# FPGA_PWR.net
KiCad netlist of a schematic drawn in Altium Designer
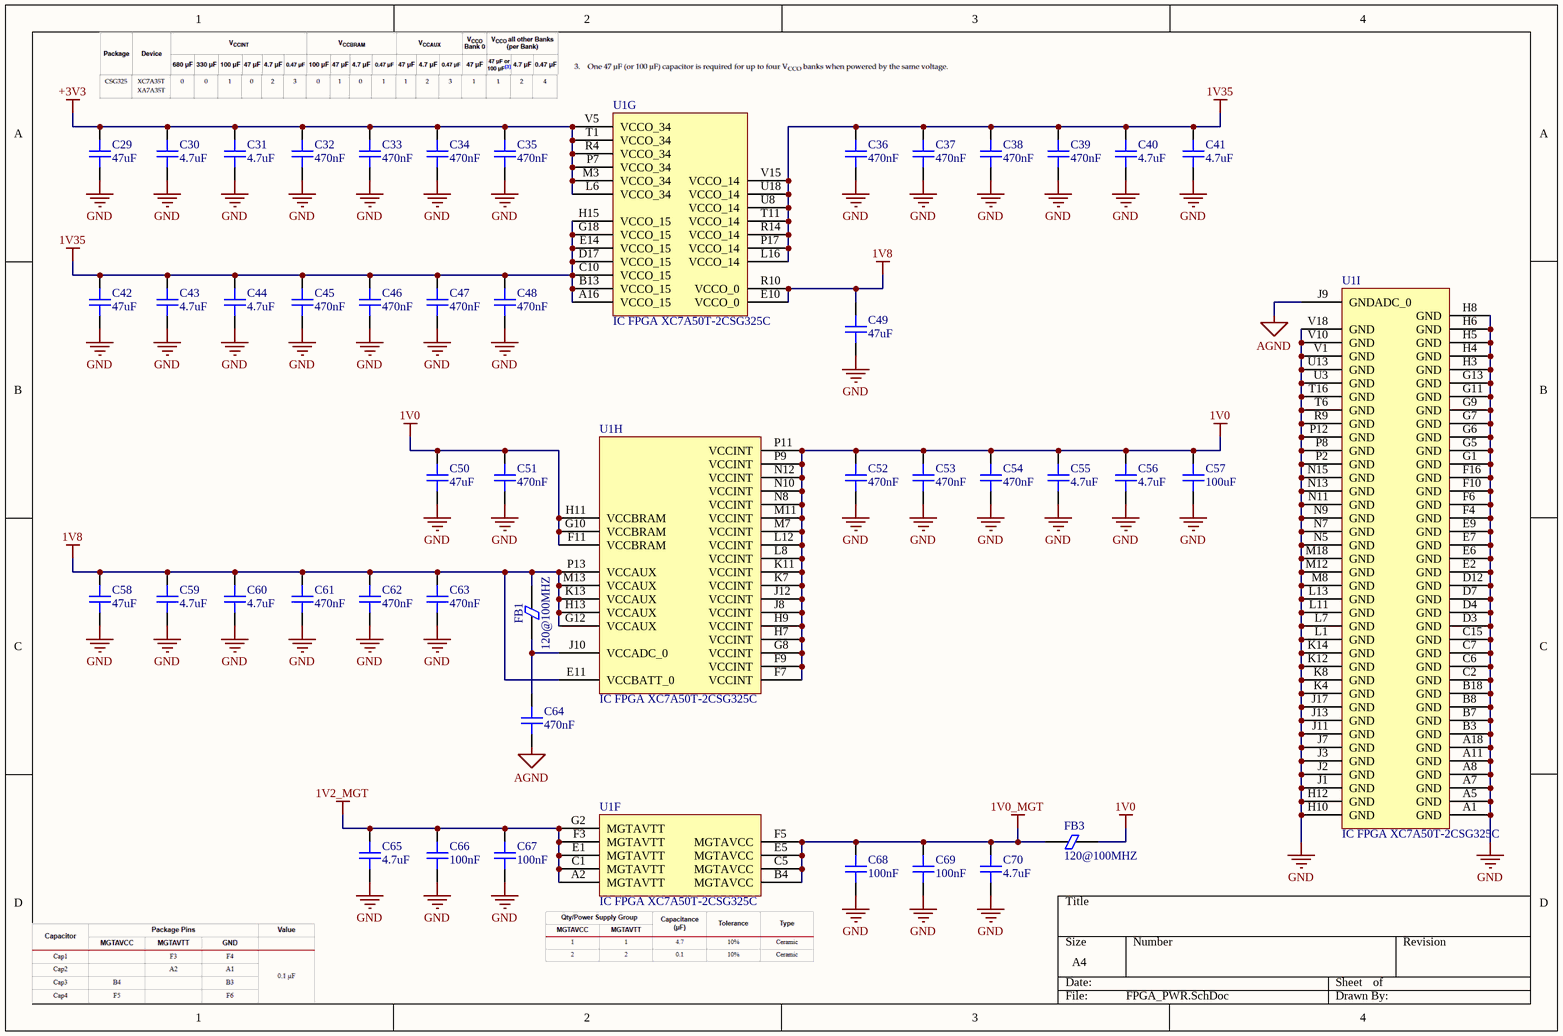
[diagram p0: FPGA_PWR.SchDoc]

(export (version "E")
  (design (tool "Eeschema 10.0.6"))
  (components
    (comp (ref "C29")
      (value "47uF")
      (footprint "GEN_C_0805")
      (libsource (lib "DSO") (part "CAP 47uF 6.3V X5R 0805"))
    )
    (comp (ref "C30")
      (value "4.7uF")
      (footprint "GEN_C_0402")
      (libsource (lib "DSO") (part "CAP 4.7uF 6.3V X5R 0402"))
    )
    (comp (ref "C31")
      (value "4.7uF")
      (footprint "GEN_C_0402")
      (libsource (lib "DSO") (part "CAP 4.7uF 6.3V X5R 0402"))
    )
    (comp (ref "C32")
      (value "470nF")
      (footprint "GEN_C_0201")
      (libsource (lib "DSO") (part "CAP 470nF 6.3V X5R 0201"))
    )
    (comp (ref "C33")
      (value "470nF")
      (footprint "GEN_C_0201")
      (libsource (lib "DSO") (part "CAP 470nF 6.3V X5R 0201"))
    )
    (comp (ref "C34")
      (value "470nF")
      (footprint "GEN_C_0201")
      (libsource (lib "DSO") (part "CAP 470nF 6.3V X5R 0201"))
    )
    (comp (ref "C35")
      (value "470nF")
      (footprint "GEN_C_0201")
      (libsource (lib "DSO") (part "CAP 470nF 6.3V X5R 0201"))
    )
    (comp (ref "C36")
      (value "470nF")
      (footprint "GEN_C_0201")
      (libsource (lib "DSO") (part "CAP 470nF 6.3V X5R 0201"))
    )
    (comp (ref "C37")
      (value "470nF")
      (footprint "GEN_C_0201")
      (libsource (lib "DSO") (part "CAP 470nF 6.3V X5R 0201"))
    )
    (comp (ref "C38")
      (value "470nF")
      (footprint "GEN_C_0201")
      (libsource (lib "DSO") (part "CAP 470nF 6.3V X5R 0201"))
    )
    (comp (ref "C39")
      (value "470nF")
      (footprint "GEN_C_0201")
      (libsource (lib "DSO") (part "CAP 470nF 6.3V X5R 0201"))
    )
    (comp (ref "C40")
      (value "4.7uF")
      (footprint "GEN_C_0402")
      (libsource (lib "DSO") (part "CAP 4.7uF 6.3V X5R 0402"))
    )
    (comp (ref "C41")
      (value "4.7uF")
      (footprint "GEN_C_0402")
      (libsource (lib "DSO") (part "CAP 4.7uF 6.3V X5R 0402"))
    )
    (comp (ref "C42")
      (value "47uF")
      (footprint "GEN_C_0805")
      (libsource (lib "DSO") (part "CAP 47uF 6.3V X5R 0805"))
    )
    (comp (ref "C43")
      (value "4.7uF")
      (footprint "GEN_C_0402")
      (libsource (lib "DSO") (part "CAP 4.7uF 6.3V X5R 0402"))
    )
    (comp (ref "C44")
      (value "4.7uF")
      (footprint "GEN_C_0402")
      (libsource (lib "DSO") (part "CAP 4.7uF 6.3V X5R 0402"))
    )
    (comp (ref "C45")
      (value "470nF")
      (footprint "GEN_C_0201")
      (libsource (lib "DSO") (part "CAP 470nF 6.3V X5R 0201"))
    )
    (comp (ref "C46")
      (value "470nF")
      (footprint "GEN_C_0201")
      (libsource (lib "DSO") (part "CAP 470nF 6.3V X5R 0201"))
    )
    (comp (ref "C47")
      (value "470nF")
      (footprint "GEN_C_0201")
      (libsource (lib "DSO") (part "CAP 470nF 6.3V X5R 0201"))
    )
    (comp (ref "C48")
      (value "470nF")
      (footprint "GEN_C_0201")
      (libsource (lib "DSO") (part "CAP 470nF 6.3V X5R 0201"))
    )
    (comp (ref "C49")
      (value "47uF")
      (footprint "GEN_C_0805")
      (libsource (lib "DSO") (part "CAP 47uF 6.3V X5R 0805"))
    )
    (comp (ref "C50")
      (value "47uF")
      (footprint "GEN_C_0805")
      (libsource (lib "DSO") (part "CAP 47uF 6.3V X5R 0805"))
    )
    (comp (ref "C51")
      (value "470nF")
      (footprint "GEN_C_0201")
      (libsource (lib "DSO") (part "CAP 470nF 6.3V X5R 0201"))
    )
    (comp (ref "C52")
      (value "470nF")
      (footprint "GEN_C_0201")
      (libsource (lib "DSO") (part "CAP 470nF 6.3V X5R 0201"))
    )
    (comp (ref "C53")
      (value "470nF")
      (footprint "GEN_C_0201")
      (libsource (lib "DSO") (part "CAP 470nF 6.3V X5R 0201"))
    )
    (comp (ref "C54")
      (value "470nF")
      (footprint "GEN_C_0201")
      (libsource (lib "DSO") (part "CAP 470nF 6.3V X5R 0201"))
    )
    (comp (ref "C55")
      (value "4.7uF")
      (footprint "GEN_C_0402")
      (libsource (lib "DSO") (part "CAP 4.7uF 6.3V X5R 0402"))
    )
    (comp (ref "C56")
      (value "4.7uF")
      (footprint "GEN_C_0402")
      (libsource (lib "DSO") (part "CAP 4.7uF 6.3V X5R 0402"))
    )
    (comp (ref "C57")
      (value "100uF")
      (footprint "GEN_C_1210")
      (libsource (lib "DSO") (part "CAP 100uF 6.3V X5R 1210"))
    )
    (comp (ref "C58")
      (value "47uF")
      (footprint "GEN_C_0805")
      (libsource (lib "DSO") (part "CAP 47uF 6.3V X5R 0805"))
    )
    (comp (ref "C59")
      (value "4.7uF")
      (footprint "GEN_C_0402")
      (libsource (lib "DSO") (part "CAP 4.7uF 6.3V X5R 0402"))
    )
    (comp (ref "C60")
      (value "4.7uF")
      (footprint "GEN_C_0402")
      (libsource (lib "DSO") (part "CAP 4.7uF 6.3V X5R 0402"))
    )
    (comp (ref "C61")
      (value "470nF")
      (footprint "GEN_C_0201")
      (libsource (lib "DSO") (part "CAP 470nF 6.3V X5R 0201"))
    )
    (comp (ref "C62")
      (value "470nF")
      (footprint "GEN_C_0201")
      (libsource (lib "DSO") (part "CAP 470nF 6.3V X5R 0201"))
    )
    (comp (ref "C63")
      (value "470nF")
      (footprint "GEN_C_0201")
      (libsource (lib "DSO") (part "CAP 470nF 6.3V X5R 0201"))
    )
    (comp (ref "C64")
      (value "470nF")
      (footprint "GEN_C_0201")
      (libsource (lib "DSO") (part "CAP 470nF 6.3V X5R 0201"))
    )
    (comp (ref "C65")
      (value "4.7uF")
      (footprint "GEN_C_0402")
      (libsource (lib "DSO") (part "CAP 4.7uF 6.3V X5R 0402"))
    )
    (comp (ref "C66")
      (value "100nF")
      (footprint "GEN_C_0201")
      (libsource (lib "DSO") (part "CAP 100nF 6.3V X5R 0201"))
    )
    (comp (ref "C67")
      (value "100nF")
      (footprint "GEN_C_0201")
      (libsource (lib "DSO") (part "CAP 100nF 6.3V X5R 0201"))
    )
    (comp (ref "C68")
      (value "100nF")
      (footprint "GEN_C_0201")
      (libsource (lib "DSO") (part "CAP 100nF 6.3V X5R 0201"))
    )
    (comp (ref "C69")
      (value "100nF")
      (footprint "GEN_C_0201")
      (libsource (lib "DSO") (part "CAP 100nF 6.3V X5R 0201"))
    )
    (comp (ref "C70")
      (value "4.7uF")
      (footprint "GEN_C_0402")
      (libsource (lib "DSO") (part "CAP 4.7uF 6.3V X5R 0402"))
    )
    (comp (ref "FB1")
      (value "120@100MHZ")
      (footprint "GEN_R_0402")
      (libsource (lib "DSO") (part "FERRITE BEAD 120 OHM 0402"))
    )
    (comp (ref "FB3")
      (value "120@100MHZ")
      (footprint "GEN_R_0402")
      (libsource (lib "DSO") (part "FERRITE BEAD 120 OHM 0402"))
    )
    (comp (ref "U1")
      (value "IC FPGA XC7A50T-2CSG325C")
      (footprint "XILINX_XC7A50T-2CSG325C")
      (description "Artix-7 FPGA, 150 User I/Os, 4 GTP, 324-Ball BGA, Speed Grade 2, Commercial Grade, Pb-Free")
      (fields (field (name "MANUFACTURER") "Xilinx") (field (name "PARTNUMBER") "XC7A35T-2CSG325C"))
      (libsource (lib "DSO") (part "IC FPGA XC7A50T-2CSG325C"))
    )
  )
  (nets
    (net (code "1") (name "+3V3") (class "Default")
      (node (ref "C29") (pin "2") (pinfunction "2_2") (pintype "passive"))
      (node (ref "C30") (pin "2") (pinfunction "2_2") (pintype "passive"))
      (node (ref "C31") (pin "2") (pinfunction "2_2") (pintype "passive"))
      (node (ref "C32") (pin "2") (pinfunction "2_2") (pintype "passive"))
      (node (ref "C33") (pin "2") (pinfunction "2_2") (pintype "passive"))
      (node (ref "C34") (pin "2") (pinfunction "2_2") (pintype "passive"))
      (node (ref "C35") (pin "2") (pinfunction "2_2") (pintype "passive"))
      (node (ref "U1") (pin "L6") (pinfunction "VCCO_34_L6") (pintype "power_in"))
      (node (ref "U1") (pin "M3") (pinfunction "VCCO_34_M3") (pintype "power_in"))
      (node (ref "U1") (pin "P7") (pinfunction "VCCO_34_P7") (pintype "power_in"))
      (node (ref "U1") (pin "R4") (pinfunction "VCCO_34_R4") (pintype "power_in"))
      (node (ref "U1") (pin "T1") (pinfunction "VCCO_34_T1") (pintype "power_in"))
      (node (ref "U1") (pin "V5") (pinfunction "VCCO_34_V5") (pintype "power_in"))
    )
    (net (code "2") (name "1V0") (class "Default")
      (node (ref "C50") (pin "2") (pinfunction "2_2") (pintype "passive"))
      (node (ref "C51") (pin "2") (pinfunction "2_2") (pintype "passive"))
      (node (ref "C52") (pin "2") (pinfunction "2_2") (pintype "passive"))
      (node (ref "C53") (pin "2") (pinfunction "2_2") (pintype "passive"))
      (node (ref "C54") (pin "2") (pinfunction "2_2") (pintype "passive"))
      (node (ref "C55") (pin "2") (pinfunction "2_2") (pintype "passive"))
      (node (ref "C56") (pin "2") (pinfunction "2_2") (pintype "passive"))
      (node (ref "C57") (pin "2") (pinfunction "2_2") (pintype "passive"))
      (node (ref "FB3") (pin "1") (pinfunction "1_1") (pintype "passive"))
      (node (ref "U1") (pin "F11") (pinfunction "VCCBRAM_F11") (pintype "power_in"))
      (node (ref "U1") (pin "F7") (pinfunction "VCCINT_F7") (pintype "power_in"))
      (node (ref "U1") (pin "F9") (pinfunction "VCCINT_F9") (pintype "power_in"))
      (node (ref "U1") (pin "G10") (pinfunction "VCCBRAM_G10") (pintype "power_in"))
      (node (ref "U1") (pin "G8") (pinfunction "VCCINT_G8") (pintype "power_in"))
      (node (ref "U1") (pin "H11") (pinfunction "VCCBRAM_H11") (pintype "power_in"))
      (node (ref "U1") (pin "H7") (pinfunction "VCCINT_H7") (pintype "power_in"))
      (node (ref "U1") (pin "H9") (pinfunction "VCCINT_H9") (pintype "power_in"))
      (node (ref "U1") (pin "J12") (pinfunction "VCCINT_J12") (pintype "power_in"))
      (node (ref "U1") (pin "J8") (pinfunction "VCCINT_J8") (pintype "power_in"))
      (node (ref "U1") (pin "K11") (pinfunction "VCCINT_K11") (pintype "power_in"))
      (node (ref "U1") (pin "K7") (pinfunction "VCCINT_K7") (pintype "power_in"))
      (node (ref "U1") (pin "L12") (pinfunction "VCCINT_L12") (pintype "power_in"))
      (node (ref "U1") (pin "L8") (pinfunction "VCCINT_L8") (pintype "power_in"))
      (node (ref "U1") (pin "M11") (pinfunction "VCCINT_M11") (pintype "power_in"))
      (node (ref "U1") (pin "M7") (pinfunction "VCCINT_M7") (pintype "power_in"))
      (node (ref "U1") (pin "N10") (pinfunction "VCCINT_N10") (pintype "power_in"))
      (node (ref "U1") (pin "N12") (pinfunction "VCCINT_N12") (pintype "power_in"))
      (node (ref "U1") (pin "N8") (pinfunction "VCCINT_N8") (pintype "power_in"))
      (node (ref "U1") (pin "P11") (pinfunction "VCCINT_P11") (pintype "power_in"))
      (node (ref "U1") (pin "P9") (pinfunction "VCCINT_P9") (pintype "power_in"))
    )
    (net (code "3") (name "1V0_MGT") (class "Default")
      (node (ref "C68") (pin "2") (pinfunction "2_2") (pintype "passive"))
      (node (ref "C69") (pin "2") (pinfunction "2_2") (pintype "passive"))
      (node (ref "C70") (pin "2") (pinfunction "2_2") (pintype "passive"))
      (node (ref "FB3") (pin "2") (pinfunction "2_2") (pintype "passive"))
      (node (ref "U1") (pin "B4") (pinfunction "MGTAVCC_B4") (pintype "power_in"))
      (node (ref "U1") (pin "C5") (pinfunction "MGTAVCC_C5") (pintype "power_in"))
      (node (ref "U1") (pin "E5") (pinfunction "MGTAVCC_E5") (pintype "power_in"))
      (node (ref "U1") (pin "F5") (pinfunction "MGTAVCC_F5") (pintype "power_in"))
    )
    (net (code "4") (name "1V2_MGT") (class "Default")
      (node (ref "C65") (pin "2") (pinfunction "2_2") (pintype "passive"))
      (node (ref "C66") (pin "2") (pinfunction "2_2") (pintype "passive"))
      (node (ref "C67") (pin "2") (pinfunction "2_2") (pintype "passive"))
      (node (ref "U1") (pin "A2") (pinfunction "MGTAVTT_A2") (pintype "power_in"))
      (node (ref "U1") (pin "C1") (pinfunction "MGTAVTT_C1") (pintype "power_in"))
      (node (ref "U1") (pin "E1") (pinfunction "MGTAVTT_E1") (pintype "power_in"))
      (node (ref "U1") (pin "F3") (pinfunction "MGTAVTT_F3") (pintype "power_in"))
      (node (ref "U1") (pin "G2") (pinfunction "MGTAVTT_G2") (pintype "power_in"))
    )
    (net (code "5") (name "1V8") (class "Default")
      (node (ref "C49") (pin "2") (pinfunction "2_2") (pintype "passive"))
      (node (ref "C58") (pin "2") (pinfunction "2_2") (pintype "passive"))
      (node (ref "C59") (pin "2") (pinfunction "2_2") (pintype "passive"))
      (node (ref "C60") (pin "2") (pinfunction "2_2") (pintype "passive"))
      (node (ref "C61") (pin "2") (pinfunction "2_2") (pintype "passive"))
      (node (ref "C62") (pin "2") (pinfunction "2_2") (pintype "passive"))
      (node (ref "C63") (pin "2") (pinfunction "2_2") (pintype "passive"))
      (node (ref "FB1") (pin "2") (pinfunction "2_2") (pintype "passive"))
      (node (ref "U1") (pin "E10") (pinfunction "VCCO_0_E10") (pintype "power_in"))
      (node (ref "U1") (pin "E11") (pinfunction "VCCBATT_0_E11") (pintype "power_in"))
      (node (ref "U1") (pin "G12") (pinfunction "VCCAUX_G12") (pintype "power_in"))
      (node (ref "U1") (pin "H13") (pinfunction "VCCAUX_H13") (pintype "power_in"))
      (node (ref "U1") (pin "K13") (pinfunction "VCCAUX_K13") (pintype "power_in"))
      (node (ref "U1") (pin "M13") (pinfunction "VCCAUX_M13") (pintype "power_in"))
      (node (ref "U1") (pin "P13") (pinfunction "VCCAUX_P13") (pintype "power_in"))
      (node (ref "U1") (pin "R10") (pinfunction "VCCO_0_R10") (pintype "power_in"))
    )
    (net (code "6") (name "1V35") (class "Default")
      (node (ref "C36") (pin "2") (pinfunction "2_2") (pintype "passive"))
      (node (ref "C37") (pin "2") (pinfunction "2_2") (pintype "passive"))
      (node (ref "C38") (pin "2") (pinfunction "2_2") (pintype "passive"))
      (node (ref "C39") (pin "2") (pinfunction "2_2") (pintype "passive"))
      (node (ref "C40") (pin "2") (pinfunction "2_2") (pintype "passive"))
      (node (ref "C41") (pin "2") (pinfunction "2_2") (pintype "passive"))
      (node (ref "C42") (pin "2") (pinfunction "2_2") (pintype "passive"))
      (node (ref "C43") (pin "2") (pinfunction "2_2") (pintype "passive"))
      (node (ref "C44") (pin "2") (pinfunction "2_2") (pintype "passive"))
      (node (ref "C45") (pin "2") (pinfunction "2_2") (pintype "passive"))
      (node (ref "C46") (pin "2") (pinfunction "2_2") (pintype "passive"))
      (node (ref "C47") (pin "2") (pinfunction "2_2") (pintype "passive"))
      (node (ref "C48") (pin "2") (pinfunction "2_2") (pintype "passive"))
      (node (ref "U1") (pin "A16") (pinfunction "VCCO_15_A16") (pintype "power_in"))
      (node (ref "U1") (pin "B13") (pinfunction "VCCO_15_B13") (pintype "power_in"))
      (node (ref "U1") (pin "C10") (pinfunction "VCCO_15_C10") (pintype "power_in"))
      (node (ref "U1") (pin "D17") (pinfunction "VCCO_15_D17") (pintype "power_in"))
      (node (ref "U1") (pin "E14") (pinfunction "VCCO_15_E14") (pintype "power_in"))
      (node (ref "U1") (pin "G18") (pinfunction "VCCO_15_G18") (pintype "power_in"))
      (node (ref "U1") (pin "H15") (pinfunction "VCCO_15_H15") (pintype "power_in"))
      (node (ref "U1") (pin "L16") (pinfunction "VCCO_14_L16") (pintype "power_in"))
      (node (ref "U1") (pin "P17") (pinfunction "VCCO_14_P17") (pintype "power_in"))
      (node (ref "U1") (pin "R14") (pinfunction "VCCO_14_R14") (pintype "power_in"))
      (node (ref "U1") (pin "T11") (pinfunction "VCCO_14_T11") (pintype "power_in"))
      (node (ref "U1") (pin "U18") (pinfunction "VCCO_14_U18") (pintype "power_in"))
      (node (ref "U1") (pin "U8") (pinfunction "VCCO_14_U8") (pintype "power_in"))
      (node (ref "U1") (pin "V15") (pinfunction "VCCO_14_V15") (pintype "power_in"))
    )
    (net (code "7") (name "AGND") (class "Default")
      (node (ref "C64") (pin "1") (pinfunction "1_1") (pintype "passive"))
      (node (ref "U1") (pin "J9") (pinfunction "GNDADC_0_J9") (pintype "power_in"))
    )
    (net (code "8") (name "GND") (class "Default")
      (node (ref "C29") (pin "1") (pinfunction "1_1") (pintype "passive"))
      (node (ref "C30") (pin "1") (pinfunction "1_1") (pintype "passive"))
      (node (ref "C31") (pin "1") (pinfunction "1_1") (pintype "passive"))
      (node (ref "C32") (pin "1") (pinfunction "1_1") (pintype "passive"))
      (node (ref "C33") (pin "1") (pinfunction "1_1") (pintype "passive"))
      (node (ref "C34") (pin "1") (pinfunction "1_1") (pintype "passive"))
      (node (ref "C35") (pin "1") (pinfunction "1_1") (pintype "passive"))
      (node (ref "C36") (pin "1") (pinfunction "1_1") (pintype "passive"))
      (node (ref "C37") (pin "1") (pinfunction "1_1") (pintype "passive"))
      (node (ref "C38") (pin "1") (pinfunction "1_1") (pintype "passive"))
      (node (ref "C39") (pin "1") (pinfunction "1_1") (pintype "passive"))
      (node (ref "C40") (pin "1") (pinfunction "1_1") (pintype "passive"))
      (node (ref "C41") (pin "1") (pinfunction "1_1") (pintype "passive"))
      (node (ref "C42") (pin "1") (pinfunction "1_1") (pintype "passive"))
      (node (ref "C43") (pin "1") (pinfunction "1_1") (pintype "passive"))
      (node (ref "C44") (pin "1") (pinfunction "1_1") (pintype "passive"))
      (node (ref "C45") (pin "1") (pinfunction "1_1") (pintype "passive"))
      (node (ref "C46") (pin "1") (pinfunction "1_1") (pintype "passive"))
      (node (ref "C47") (pin "1") (pinfunction "1_1") (pintype "passive"))
      (node (ref "C48") (pin "1") (pinfunction "1_1") (pintype "passive"))
      (node (ref "C49") (pin "1") (pinfunction "1_1") (pintype "passive"))
      (node (ref "C50") (pin "1") (pinfunction "1_1") (pintype "passive"))
      (node (ref "C51") (pin "1") (pinfunction "1_1") (pintype "passive"))
      (node (ref "C52") (pin "1") (pinfunction "1_1") (pintype "passive"))
      (node (ref "C53") (pin "1") (pinfunction "1_1") (pintype "passive"))
      (node (ref "C54") (pin "1") (pinfunction "1_1") (pintype "passive"))
      (node (ref "C55") (pin "1") (pinfunction "1_1") (pintype "passive"))
      (node (ref "C56") (pin "1") (pinfunction "1_1") (pintype "passive"))
      (node (ref "C57") (pin "1") (pinfunction "1_1") (pintype "passive"))
      (node (ref "C58") (pin "1") (pinfunction "1_1") (pintype "passive"))
      (node (ref "C59") (pin "1") (pinfunction "1_1") (pintype "passive"))
      (node (ref "C60") (pin "1") (pinfunction "1_1") (pintype "passive"))
      (node (ref "C61") (pin "1") (pinfunction "1_1") (pintype "passive"))
      (node (ref "C62") (pin "1") (pinfunction "1_1") (pintype "passive"))
      (node (ref "C63") (pin "1") (pinfunction "1_1") (pintype "passive"))
      (node (ref "C65") (pin "1") (pinfunction "1_1") (pintype "passive"))
      (node (ref "C66") (pin "1") (pinfunction "1_1") (pintype "passive"))
      (node (ref "C67") (pin "1") (pinfunction "1_1") (pintype "passive"))
      (node (ref "C68") (pin "1") (pinfunction "1_1") (pintype "passive"))
      (node (ref "C69") (pin "1") (pinfunction "1_1") (pintype "passive"))
      (node (ref "C70") (pin "1") (pinfunction "1_1") (pintype "passive"))
      (node (ref "U1") (pin "A1") (pinfunction "GND_A1") (pintype "power_in"))
      (node (ref "U1") (pin "A11") (pinfunction "GND_A11") (pintype "power_in"))
      (node (ref "U1") (pin "A18") (pinfunction "GND_A18") (pintype "power_in"))
      (node (ref "U1") (pin "A5") (pinfunction "GND_A5") (pintype "power_in"))
      (node (ref "U1") (pin "A7") (pinfunction "GND_A7") (pintype "power_in"))
      (node (ref "U1") (pin "A8") (pinfunction "GND_A8") (pintype "power_in"))
      (node (ref "U1") (pin "B18") (pinfunction "GND_B18") (pintype "power_in"))
      (node (ref "U1") (pin "B3") (pinfunction "GND_B3") (pintype "power_in"))
      (node (ref "U1") (pin "B7") (pinfunction "GND_B7") (pintype "power_in"))
      (node (ref "U1") (pin "B8") (pinfunction "GND_B8") (pintype "power_in"))
      (node (ref "U1") (pin "C15") (pinfunction "GND_C15") (pintype "power_in"))
      (node (ref "U1") (pin "C2") (pinfunction "GND_C2") (pintype "power_in"))
      (node (ref "U1") (pin "C6") (pinfunction "GND_C6") (pintype "power_in"))
      (node (ref "U1") (pin "C7") (pinfunction "GND_C7") (pintype "power_in"))
      (node (ref "U1") (pin "D12") (pinfunction "GND_D12") (pintype "power_in"))
      (node (ref "U1") (pin "D3") (pinfunction "GND_D3") (pintype "power_in"))
      (node (ref "U1") (pin "D4") (pinfunction "GND_D4") (pintype "power_in"))
      (node (ref "U1") (pin "D7") (pinfunction "GND_D7") (pintype "power_in"))
      (node (ref "U1") (pin "E2") (pinfunction "GND_E2") (pintype "power_in"))
      (node (ref "U1") (pin "E6") (pinfunction "GND_E6") (pintype "power_in"))
      (node (ref "U1") (pin "E7") (pinfunction "GND_E7") (pintype "power_in"))
      (node (ref "U1") (pin "E9") (pinfunction "GND_E9") (pintype "power_in"))
      (node (ref "U1") (pin "F10") (pinfunction "GND_F10") (pintype "power_in"))
      (node (ref "U1") (pin "F16") (pinfunction "GND_F16") (pintype "power_in"))
      (node (ref "U1") (pin "F4") (pinfunction "GND_F4") (pintype "power_in"))
      (node (ref "U1") (pin "F6") (pinfunction "GND_F6") (pintype "power_in"))
      (node (ref "U1") (pin "G1") (pinfunction "GND_G1") (pintype "power_in"))
      (node (ref "U1") (pin "G11") (pinfunction "GND_G11") (pintype "power_in"))
      (node (ref "U1") (pin "G13") (pinfunction "GND_G13") (pintype "power_in"))
      (node (ref "U1") (pin "G5") (pinfunction "GND_G5") (pintype "power_in"))
      (node (ref "U1") (pin "G6") (pinfunction "GND_G6") (pintype "power_in"))
      (node (ref "U1") (pin "G7") (pinfunction "GND_G7") (pintype "power_in"))
      (node (ref "U1") (pin "G9") (pinfunction "GND_G9") (pintype "power_in"))
      (node (ref "U1") (pin "H10") (pinfunction "GND_H10") (pintype "power_in"))
      (node (ref "U1") (pin "H12") (pinfunction "GND_H12") (pintype "power_in"))
      (node (ref "U1") (pin "H3") (pinfunction "GND_H3") (pintype "power_in"))
      (node (ref "U1") (pin "H4") (pinfunction "GND_H4") (pintype "power_in"))
      (node (ref "U1") (pin "H5") (pinfunction "GND_H5") (pintype "power_in"))
      (node (ref "U1") (pin "H6") (pinfunction "GND_H6") (pintype "power_in"))
      (node (ref "U1") (pin "H8") (pinfunction "GND_H8") (pintype "power_in"))
      (node (ref "U1") (pin "J1") (pinfunction "GND_J1") (pintype "power_in"))
      (node (ref "U1") (pin "J11") (pinfunction "GND_J11") (pintype "power_in"))
      (node (ref "U1") (pin "J13") (pinfunction "GND_J13") (pintype "power_in"))
      (node (ref "U1") (pin "J17") (pinfunction "GND_J17") (pintype "power_in"))
      (node (ref "U1") (pin "J2") (pinfunction "GND_J2") (pintype "power_in"))
      (node (ref "U1") (pin "J3") (pinfunction "GND_J3") (pintype "power_in"))
      (node (ref "U1") (pin "J7") (pinfunction "GND_J7") (pintype "power_in"))
      (node (ref "U1") (pin "K12") (pinfunction "GND_K12") (pintype "power_in"))
      (node (ref "U1") (pin "K14") (pinfunction "GND_K14") (pintype "power_in"))
      (node (ref "U1") (pin "K4") (pinfunction "GND_K4") (pintype "power_in"))
      (node (ref "U1") (pin "K8") (pinfunction "GND_K8") (pintype "power_in"))
      (node (ref "U1") (pin "L1") (pinfunction "GND_L1") (pintype "power_in"))
      (node (ref "U1") (pin "L11") (pinfunction "GND_L11") (pintype "power_in"))
      (node (ref "U1") (pin "L13") (pinfunction "GND_L13") (pintype "power_in"))
      (node (ref "U1") (pin "L7") (pinfunction "GND_L7") (pintype "power_in"))
      (node (ref "U1") (pin "M12") (pinfunction "GND_M12") (pintype "power_in"))
      (node (ref "U1") (pin "M18") (pinfunction "GND_M18") (pintype "power_in"))
      (node (ref "U1") (pin "M8") (pinfunction "GND_M8") (pintype "power_in"))
      (node (ref "U1") (pin "N11") (pinfunction "GND_N11") (pintype "power_in"))
      (node (ref "U1") (pin "N13") (pinfunction "GND_N13") (pintype "power_in"))
      (node (ref "U1") (pin "N15") (pinfunction "GND_N15") (pintype "power_in"))
      (node (ref "U1") (pin "N5") (pinfunction "GND_N5") (pintype "power_in"))
      (node (ref "U1") (pin "N7") (pinfunction "GND_N7") (pintype "power_in"))
      (node (ref "U1") (pin "N9") (pinfunction "GND_N9") (pintype "power_in"))
      (node (ref "U1") (pin "P12") (pinfunction "GND_P12") (pintype "power_in"))
      (node (ref "U1") (pin "P2") (pinfunction "GND_P2") (pintype "power_in"))
      (node (ref "U1") (pin "P8") (pinfunction "GND_P8") (pintype "power_in"))
      (node (ref "U1") (pin "R9") (pinfunction "GND_R9") (pintype "power_in"))
      (node (ref "U1") (pin "T16") (pinfunction "GND_T16") (pintype "power_in"))
      (node (ref "U1") (pin "T6") (pinfunction "GND_T6") (pintype "power_in"))
      (node (ref "U1") (pin "U13") (pinfunction "GND_U13") (pintype "power_in"))
      (node (ref "U1") (pin "U3") (pinfunction "GND_U3") (pintype "power_in"))
      (node (ref "U1") (pin "V1") (pinfunction "GND_V1") (pintype "power_in"))
      (node (ref "U1") (pin "V10") (pinfunction "GND_V10") (pintype "power_in"))
      (node (ref "U1") (pin "V18") (pinfunction "GND_V18") (pintype "power_in"))
    )
    (net (code "9") (name "Net-(U1H-VCCADC_0)") (class "Default")
      (node (ref "C64") (pin "2") (pinfunction "2_2") (pintype "passive"))
      (node (ref "FB1") (pin "1") (pinfunction "1_1") (pintype "passive"))
      (node (ref "U1") (pin "J10") (pinfunction "VCCADC_0_J10") (pintype "power_in"))
    )
  )
)
